# Dumping_servo.net
KiCad netlist of a schematic drawn in Altium Designer
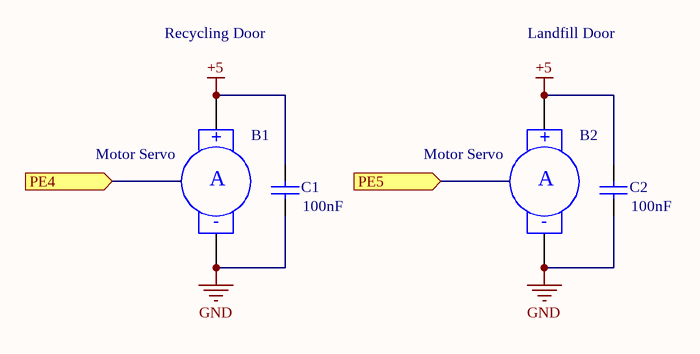
[diagram p0: Dumping_servo.SchDoc]

(export (version "E")
  (design (tool "Eeschema 10.0.6"))
  (components
    (comp (ref "B1")
      (value "Motor Servo")
      (footprint "RAD-0.4")
      (description "Servo Motor")
      (fields (field (name "PUBLISHER") "Altium Limited"))
      (libsource (lib "Miscellaneous Devices") (part "Motor Servo"))
    )
    (comp (ref "B2")
      (value "Motor Servo")
      (footprint "RAD-0.4")
      (description "Servo Motor")
      (fields (field (name "PUBLISHER") "Altium Limited"))
      (libsource (lib "Miscellaneous Devices") (part "Motor Servo"))
    )
    (comp (ref "C1")
      (value "100nF")
      (footprint "RAD-0.3")
      (description "Capacitor")
      (fields (field (name "Comment") "Cap") (field (name "PUBLISHER") "Altium Limited"))
      (libsource (lib "Miscellaneous Devices") (part "Cap"))
    )
    (comp (ref "C2")
      (value "100nF")
      (footprint "RAD-0.3")
      (description "Capacitor")
      (fields (field (name "Comment") "Cap") (field (name "PUBLISHER") "Altium Limited"))
      (libsource (lib "Miscellaneous Devices") (part "Cap"))
    )
  )
  (nets
    (net (code "1") (name "+5") (class "Default")
      (node (ref "B1") (pin "1") (pinfunction "+_1") (pintype "passive"))
      (node (ref "B2") (pin "1") (pinfunction "+_1") (pintype "passive"))
      (node (ref "C1") (pin "2") (pinfunction "2_2") (pintype "passive"))
      (node (ref "C2") (pin "2") (pinfunction "2_2") (pintype "passive"))
    )
    (net (code "4") (name "GND") (class "Default")
      (node (ref "B1") (pin "2") (pinfunction "-_2") (pintype "passive"))
      (node (ref "B2") (pin "2") (pinfunction "-_2") (pintype "passive"))
      (node (ref "C1") (pin "1") (pinfunction "1_1") (pintype "passive"))
      (node (ref "C2") (pin "1") (pinfunction "1_1") (pintype "passive"))
    )
  )
)
